# Wheelmod_rs485.net
KiCad netlist of a schematic drawn in EAGLE
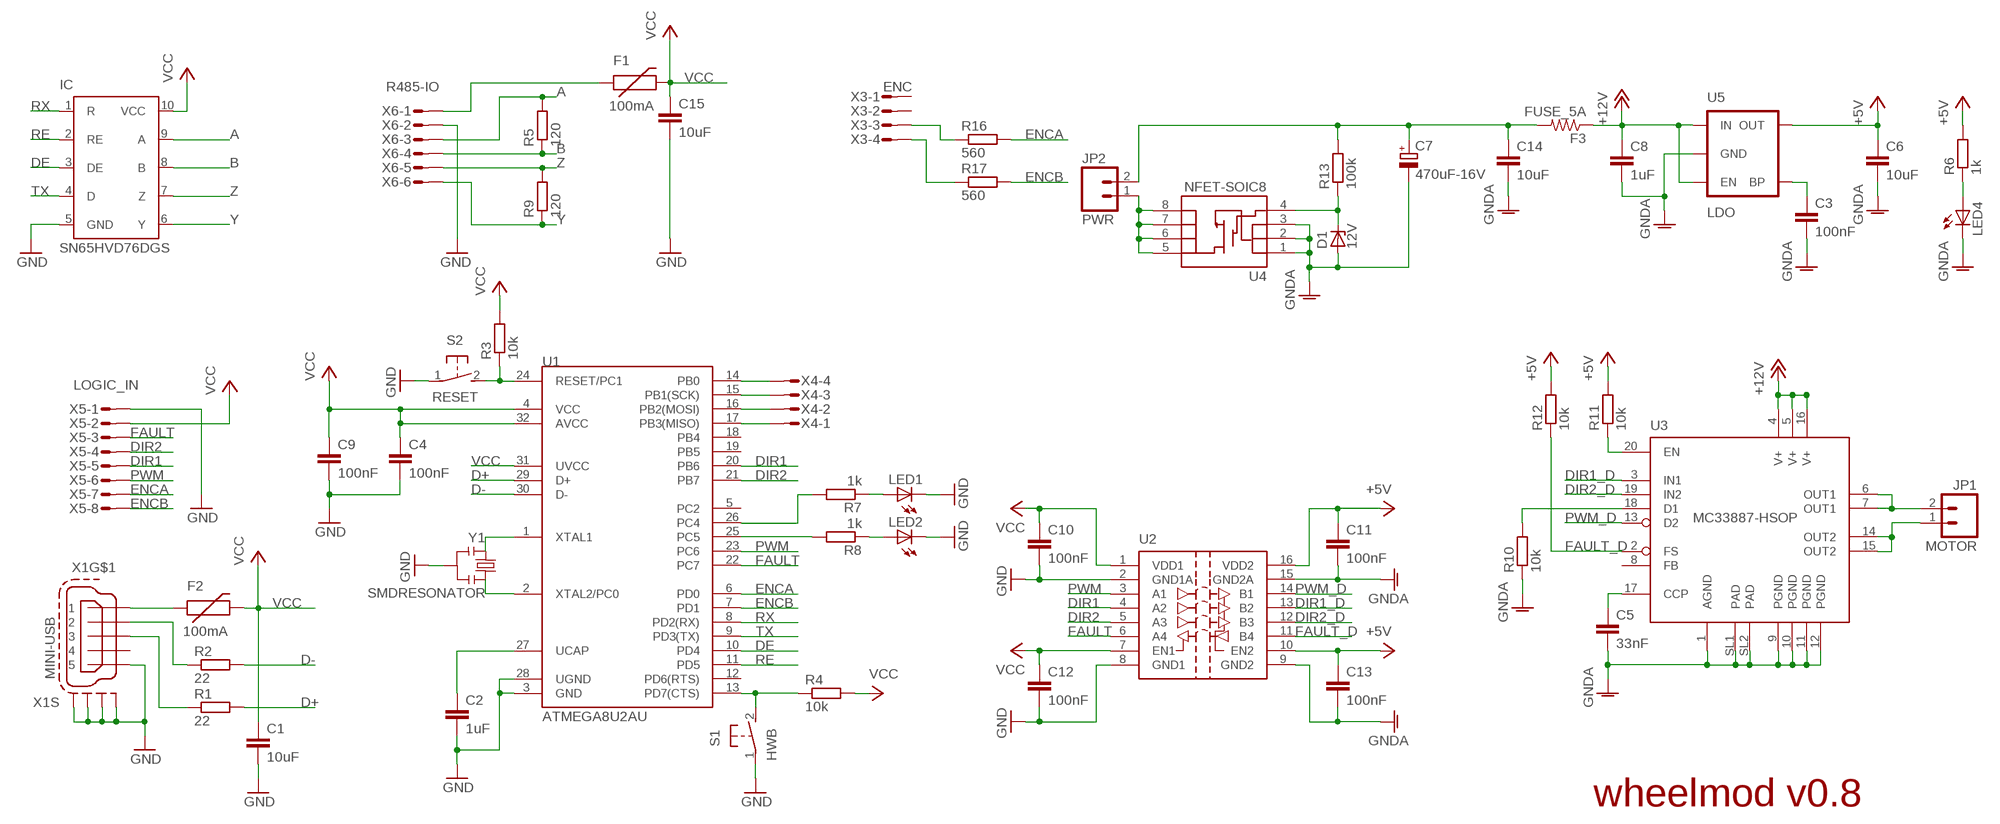
[diagram p0: schematic, sheet 1]

(export (version "E")
  (design (tool "Eeschema 10.0.6"))
  (components
    (comp (ref "C1")
      (value "10uF")
      (footprint "eagle-import:C1206K")
      (libsource (lib "eagle-import") (part "C-EUC1206K"))
    )
    (comp (ref "C2")
      (value "1uF")
      (footprint "eagle-import:C0603K")
      (libsource (lib "eagle-import") (part "C-EUC0603K"))
    )
    (comp (ref "C3")
      (value "100nF")
      (footprint "eagle-import:C0603K")
      (libsource (lib "eagle-import") (part "C-EUC0603K"))
    )
    (comp (ref "C4")
      (value "100nF")
      (footprint "eagle-import:C0603K")
      (libsource (lib "eagle-import") (part "C-EUC0603K"))
    )
    (comp (ref "C5")
      (value "33nF")
      (footprint "eagle-import:C0603K")
      (libsource (lib "eagle-import") (part "C-EUC0603K"))
    )
    (comp (ref "C6")
      (value "10uF")
      (footprint "eagle-import:C1206K")
      (libsource (lib "eagle-import") (part "C-EUC1206K"))
    )
    (comp (ref "C7")
      (value "470uF-16V")
      (footprint "eagle-import:E3,5-8")
      (libsource (lib "eagle-import") (part "CPOL-EUE3.5-8"))
    )
    (comp (ref "C8")
      (value "1uF")
      (footprint "eagle-import:C0603K")
      (libsource (lib "eagle-import") (part "C-EUC0603K"))
    )
    (comp (ref "C9")
      (value "100nF")
      (footprint "eagle-import:C0603K")
      (libsource (lib "eagle-import") (part "C-EUC0603K"))
    )
    (comp (ref "C10")
      (value "100nF")
      (footprint "eagle-import:C0603K")
      (libsource (lib "eagle-import") (part "C-EUC0603K"))
    )
    (comp (ref "C11")
      (value "100nF")
      (footprint "eagle-import:C0603K")
      (libsource (lib "eagle-import") (part "C-EUC0603K"))
    )
    (comp (ref "C12")
      (value "100nF")
      (footprint "eagle-import:C0603K")
      (libsource (lib "eagle-import") (part "C-EUC0603K"))
    )
    (comp (ref "C13")
      (value "100nF")
      (footprint "eagle-import:C0603K")
      (libsource (lib "eagle-import") (part "C-EUC0603K"))
    )
    (comp (ref "C14")
      (value "10uF")
      (footprint "eagle-import:C1206K")
      (libsource (lib "eagle-import") (part "C-EUC1206K"))
    )
    (comp (ref "C15")
      (value "10uF")
      (footprint "eagle-import:C1206K")
      (libsource (lib "eagle-import") (part "C-EUC1206K"))
    )
    (comp (ref "D1")
      (value "12V")
      (footprint "eagle-import:SOD123")
      (libsource (lib "eagle-import") (part "ZENER-DIODESOD123"))
    )
    (comp (ref "F1")
      (value "100mA")
      (footprint "eagle-import:PTC-1206")
      (libsource (lib "eagle-import") (part "PTCSMD"))
    )
    (comp (ref "F2")
      (value "100mA")
      (footprint "eagle-import:PTC-1206")
      (libsource (lib "eagle-import") (part "PTCSMD"))
    )
    (comp (ref "F3")
      (value "FUSE_5A")
      (footprint "eagle-import:R1206")
      (libsource (lib "eagle-import") (part "R-US_R1206"))
    )
    (comp (ref "JP1")
      (value "MOTOR")
      (footprint "eagle-import:SCREWTERMINAL-3.5MM-2")
      (libsource (lib "eagle-import") (part "M023.5MM"))
    )
    (comp (ref "JP2")
      (value "PWR")
      (footprint "eagle-import:SCREWTERMINAL-3.5MM-2")
      (libsource (lib "eagle-import") (part "M023.5MM"))
    )
    (comp (ref "LED1")
      (value "LEDCHIP-LED0603")
      (footprint "eagle-import:CHIP-LED0603")
      (libsource (lib "eagle-import") (part "LEDCHIP-LED0603"))
    )
    (comp (ref "LED2")
      (value "LEDCHIP-LED0603")
      (footprint "eagle-import:CHIP-LED0603")
      (libsource (lib "eagle-import") (part "LEDCHIP-LED0603"))
    )
    (comp (ref "LED4")
      (value "LEDCHIP-LED0603")
      (footprint "eagle-import:CHIP-LED0603")
      (libsource (lib "eagle-import") (part "LEDCHIP-LED0603"))
    )
    (comp (ref "R1")
      (value "22")
      (footprint "eagle-import:R0603")
      (libsource (lib "eagle-import") (part "R-EU_R0603"))
    )
    (comp (ref "R2")
      (value "22")
      (footprint "eagle-import:R0603")
      (libsource (lib "eagle-import") (part "R-EU_R0603"))
    )
    (comp (ref "R3")
      (value "10k")
      (footprint "eagle-import:R0603")
      (libsource (lib "eagle-import") (part "R-EU_R0603"))
    )
    (comp (ref "R4")
      (value "10k")
      (footprint "eagle-import:R0603")
      (libsource (lib "eagle-import") (part "R-EU_R0603"))
    )
    (comp (ref "R5")
      (value "120")
      (footprint "eagle-import:R0603")
      (libsource (lib "eagle-import") (part "R-EU_R0603"))
    )
    (comp (ref "R6")
      (value "1k")
      (footprint "eagle-import:R0603")
      (libsource (lib "eagle-import") (part "R-EU_R0603"))
    )
    (comp (ref "R7")
      (value "1k")
      (footprint "eagle-import:R0603")
      (libsource (lib "eagle-import") (part "R-EU_R0603"))
    )
    (comp (ref "R8")
      (value "1k")
      (footprint "eagle-import:R0603")
      (libsource (lib "eagle-import") (part "R-EU_R0603"))
    )
    (comp (ref "R9")
      (value "120")
      (footprint "eagle-import:R0603")
      (libsource (lib "eagle-import") (part "R-EU_R0603"))
    )
    (comp (ref "R10")
      (value "10k")
      (footprint "eagle-import:R0603")
      (libsource (lib "eagle-import") (part "R-EU_R0603"))
    )
    (comp (ref "R11")
      (value "10k")
      (footprint "eagle-import:R0603")
      (libsource (lib "eagle-import") (part "R-EU_R0603"))
    )
    (comp (ref "R12")
      (value "10k")
      (footprint "eagle-import:R0603")
      (libsource (lib "eagle-import") (part "R-EU_R0603"))
    )
    (comp (ref "R13")
      (value "100k")
      (footprint "eagle-import:R0603")
      (libsource (lib "eagle-import") (part "R-EU_R0603"))
    )
    (comp (ref "R16")
      (value "560")
      (footprint "eagle-import:R0603")
      (libsource (lib "eagle-import") (part "R-EU_R0603"))
    )
    (comp (ref "R17")
      (value "560")
      (footprint "eagle-import:R0603")
      (libsource (lib "eagle-import") (part "R-EU_R0603"))
    )
    (comp (ref "S1")
      (value "HWB")
      (footprint "eagle-import:ADTSM3")
      (libsource (lib "eagle-import") (part "ADTSM3"))
    )
    (comp (ref "S2")
      (value "RESET")
      (footprint "eagle-import:ADTSM3")
      (libsource (lib "eagle-import") (part "ADTSM3"))
    )
    (comp (ref "U$1")
      (value "SN65HVF76DGS")
      (footprint "eagle-import:MSOP10")
      (libsource (lib "eagle-import") (part "SN65HVF76DGS"))
    )
    (comp (ref "U1")
      (value "ATMEGA8U2AU")
      (footprint "eagle-import:TQFP32-08")
      (libsource (lib "eagle-import") (part "ATMEGA8U2AU"))
    )
    (comp (ref "U2")
      (value "SI8441IS1")
      (footprint "eagle-import:SO16")
      (libsource (lib "eagle-import") (part "SI8441IS1"))
    )
    (comp (ref "U3")
      (value "MC33887-HSOP")
      (footprint "eagle-import:HSOP")
      (libsource (lib "eagle-import") (part "MC33887-HSOP"))
    )
    (comp (ref "U4")
      (value "NFET-SOIC8")
      (footprint "eagle-import:SO08")
      (libsource (lib "eagle-import") (part "MOSFET-NCHANNEL-SOIC8"))
    )
    (comp (ref "U5")
      (value "LDO")
      (footprint "eagle-import:SOT23-5")
      (libsource (lib "eagle-import") (part "V_REG_LDOSMD"))
    )
    (comp (ref "X1")
      (value "MINI-USB")
      (footprint "eagle-import:32005-301")
      (libsource (lib "eagle-import") (part "MINI-USB-SCHIELD-32005-301"))
    )
    (comp (ref "X3")
      (value "ENC")
      (footprint "eagle-import:MICROMATCH-4")
      (fields (field (name "MPN") "7-215464-4"))
      (libsource (lib "eagle-import") (part "MICROMATCH-4"))
    )
    (comp (ref "X4")
      (value "MICROMATCH-4")
      (footprint "eagle-import:MICROMATCH-4")
      (fields (field (name "MPN") "7-215464-4"))
      (libsource (lib "eagle-import") (part "MICROMATCH-4"))
    )
    (comp (ref "X5")
      (value "LOGIC_IN")
      (footprint "eagle-import:MICROMATCH-8")
      (fields (field (name "MF") "FARNELL") (field (name "MPN") "7-215464-8"))
      (libsource (lib "eagle-import") (part "MICROMATCH-8"))
    )
    (comp (ref "X6")
      (value "R485-IO")
      (footprint "eagle-import:MICROMATCH-6")
      (fields (field (name "MPN") "7-215464-6"))
      (libsource (lib "eagle-import") (part "MICROMATCH-6"))
    )
    (comp (ref "Y1")
      (value "SMDRESONATOR")
      (footprint "eagle-import:PBRC-M")
      (libsource (lib "eagle-import") (part "SMDRESONATOR45X20"))
    )
  )
  (nets
    (net (code "1") (name "+5V") (class "Default")
      (node (ref "C11") (pin "1") (pinfunction "1_1") (pintype "passive"))
      (node (ref "C13") (pin "1") (pinfunction "1_1") (pintype "passive"))
      (node (ref "C6") (pin "1") (pinfunction "1_1") (pintype "passive"))
      (node (ref "R11") (pin "2") (pinfunction "2_2") (pintype "passive"))
      (node (ref "R12") (pin "2") (pinfunction "2_2") (pintype "passive"))
      (node (ref "R6") (pin "2") (pinfunction "2_2") (pintype "passive"))
      (node (ref "U2") (pin "10") (pinfunction "EN2_10") (pintype "input"))
      (node (ref "U2") (pin "16") (pinfunction "VDD2_16") (pintype "power_in"))
      (node (ref "U5") (pin "5") (pinfunction "OUT_5") (pintype "passive"))
    )
    (net (code "2") (name "+12V") (class "Default")
      (node (ref "C8") (pin "1") (pinfunction "1_1") (pintype "passive"))
      (node (ref "F3") (pin "1") (pinfunction "1_1") (pintype "passive"))
      (node (ref "U3") (pin "16") (pinfunction "V+_16") (pintype "power_in"))
      (node (ref "U3") (pin "4") (pinfunction "V+_4") (pintype "power_in"))
      (node (ref "U3") (pin "5") (pinfunction "V+_5") (pintype "power_in"))
      (node (ref "U5") (pin "1") (pinfunction "IN_1") (pintype "input"))
      (node (ref "U5") (pin "3") (pinfunction "EN_3") (pintype "input"))
    )
    (net (code "3") (name "/A") (class "Default")
      (node (ref "R5") (pin "2") (pinfunction "2_2") (pintype "passive"))
      (node (ref "U$1") (pin "9") (pinfunction "A_9") (pintype "input"))
      (node (ref "X6") (pin "3") (pinfunction "S_3") (pintype "passive"))
    )
    (net (code "4") (name "/B") (class "Default")
      (node (ref "R5") (pin "1") (pinfunction "1_1") (pintype "passive"))
      (node (ref "U$1") (pin "8") (pinfunction "B_8") (pintype "input"))
      (node (ref "X6") (pin "4") (pinfunction "S_4") (pintype "passive"))
    )
    (net (code "5") (name "/D+") (class "Default")
      (node (ref "R1") (pin "2") (pinfunction "2_2") (pintype "passive"))
      (node (ref "U1") (pin "29") (pinfunction "D+_29") (pintype "bidirectional"))
    )
    (net (code "6") (name "/D-") (class "Default")
      (node (ref "R2") (pin "2") (pinfunction "2_2") (pintype "passive"))
      (node (ref "U1") (pin "30") (pinfunction "D-_30") (pintype "bidirectional"))
    )
    (net (code "7") (name "/DE") (class "Default")
      (node (ref "U$1") (pin "3") (pinfunction "DE_3") (pintype "input"))
      (node (ref "U1") (pin "10") (pinfunction "PD4_10") (pintype "bidirectional"))
    )
    (net (code "8") (name "/DIR1") (class "Default")
      (node (ref "U1") (pin "20") (pinfunction "PB6_20") (pintype "bidirectional"))
      (node (ref "U2") (pin "4") (pinfunction "A2_4") (pintype "input"))
      (node (ref "X5") (pin "5") (pinfunction "S_5") (pintype "passive"))
    )
    (net (code "9") (name "/DIR1_D") (class "Default")
      (node (ref "U2") (pin "13") (pinfunction "B2_13") (pintype "output"))
      (node (ref "U3") (pin "3") (pinfunction "IN1_3") (pintype "input"))
    )
    (net (code "10") (name "/DIR2") (class "Default")
      (node (ref "U1") (pin "21") (pinfunction "PB7_21") (pintype "bidirectional"))
      (node (ref "U2") (pin "5") (pinfunction "A3_5") (pintype "input"))
      (node (ref "X5") (pin "4") (pinfunction "S_4") (pintype "passive"))
    )
    (net (code "11") (name "/DIR2_D") (class "Default")
      (node (ref "U2") (pin "12") (pinfunction "B3_12") (pintype "output"))
      (node (ref "U3") (pin "19") (pinfunction "IN2_19") (pintype "input"))
    )
    (net (code "12") (name "/ENCA") (class "Default")
      (node (ref "R16") (pin "2") (pinfunction "2_2") (pintype "passive"))
      (node (ref "U1") (pin "6") (pinfunction "PD0_6") (pintype "bidirectional"))
      (node (ref "X5") (pin "7") (pinfunction "S_7") (pintype "passive"))
    )
    (net (code "13") (name "/ENCB") (class "Default")
      (node (ref "R17") (pin "2") (pinfunction "2_2") (pintype "passive"))
      (node (ref "U1") (pin "7") (pinfunction "PD1_7") (pintype "bidirectional"))
      (node (ref "X5") (pin "8") (pinfunction "S_8") (pintype "passive"))
    )
    (net (code "14") (name "/FAULT") (class "Default")
      (node (ref "U1") (pin "22") (pinfunction "PC7_22") (pintype "bidirectional"))
      (node (ref "U2") (pin "6") (pinfunction "A4_6") (pintype "input"))
      (node (ref "X5") (pin "3") (pinfunction "S_3") (pintype "passive"))
    )
    (net (code "15") (name "/FAULT_D") (class "Default")
      (node (ref "R12") (pin "1") (pinfunction "1_1") (pintype "passive"))
      (node (ref "U2") (pin "11") (pinfunction "B4_11") (pintype "output"))
      (node (ref "U3") (pin "2") (pinfunction "FS_2") (pintype "open_collector"))
    )
    (net (code "16") (name "/PWM") (class "Default")
      (node (ref "U1") (pin "23") (pinfunction "PC6_23") (pintype "bidirectional"))
      (node (ref "U2") (pin "3") (pinfunction "A1_3") (pintype "input"))
      (node (ref "X5") (pin "6") (pinfunction "S_6") (pintype "passive"))
    )
    (net (code "17") (name "/PWM_D") (class "Default")
      (node (ref "U2") (pin "14") (pinfunction "B1_14") (pintype "output"))
      (node (ref "U3") (pin "13") (pinfunction "D2_13") (pintype "input"))
    )
    (net (code "18") (name "/RE") (class "Default")
      (node (ref "U$1") (pin "2") (pinfunction "RE_2") (pintype "input"))
      (node (ref "U1") (pin "11") (pinfunction "PD5_11") (pintype "bidirectional"))
    )
    (net (code "19") (name "/RX") (class "Default")
      (node (ref "U$1") (pin "1") (pinfunction "R_1") (pintype "output"))
      (node (ref "U1") (pin "8") (pinfunction "PD2(RX)_8") (pintype "bidirectional"))
    )
    (net (code "20") (name "/TX") (class "Default")
      (node (ref "U$1") (pin "4") (pinfunction "D_4") (pintype "input"))
      (node (ref "U1") (pin "9") (pinfunction "PD3(TX)_9") (pintype "bidirectional"))
    )
    (net (code "21") (name "/Y") (class "Default")
      (node (ref "R9") (pin "1") (pinfunction "1_1") (pintype "passive"))
      (node (ref "U$1") (pin "6") (pinfunction "Y_6") (pintype "output"))
      (node (ref "X6") (pin "6") (pinfunction "S_6") (pintype "passive"))
    )
    (net (code "22") (name "/Z") (class "Default")
      (node (ref "R9") (pin "2") (pinfunction "2_2") (pintype "passive"))
      (node (ref "U$1") (pin "7") (pinfunction "Z_7") (pintype "output"))
      (node (ref "X6") (pin "5") (pinfunction "S_5") (pintype "passive"))
    )
    (net (code "23") (name "GND") (class "Default")
      (node (ref "C1") (pin "2") (pinfunction "2_2") (pintype "passive"))
      (node (ref "C10") (pin "2") (pinfunction "2_2") (pintype "passive"))
      (node (ref "C12") (pin "2") (pinfunction "2_2") (pintype "passive"))
      (node (ref "C15") (pin "2") (pinfunction "2_2") (pintype "passive"))
      (node (ref "C2") (pin "2") (pinfunction "2_2") (pintype "passive"))
      (node (ref "C4") (pin "2") (pinfunction "2_2") (pintype "passive"))
      (node (ref "C9") (pin "2") (pinfunction "2_2") (pintype "passive"))
      (node (ref "LED1") (pin "C") (pinfunction "C_C") (pintype "passive"))
      (node (ref "LED2") (pin "C") (pinfunction "C_C") (pintype "passive"))
      (node (ref "S1") (pin "1") (pinfunction "1_1") (pintype "passive"))
      (node (ref "S2") (pin "1") (pinfunction "1_1") (pintype "passive"))
      (node (ref "U$1") (pin "5") (pinfunction "GND_5") (pintype "power_in"))
      (node (ref "U1") (pin "28") (pinfunction "UGND_28") (pintype "bidirectional"))
      (node (ref "U1") (pin "3") (pinfunction "GND_3") (pintype "bidirectional"))
      (node (ref "U2") (pin "2") (pinfunction "GND1A_2") (pintype "power_in"))
      (node (ref "U2") (pin "8") (pinfunction "GND1_8") (pintype "power_in"))
      (node (ref "X1") (pin "5") (pinfunction "5_5") (pintype "passive"))
      (node (ref "X1") (pin "M1") (pinfunction "S1_M1") (pintype "passive"))
      (node (ref "X1") (pin "M2") (pinfunction "S2_M2") (pintype "passive"))
      (node (ref "X1") (pin "M3") (pinfunction "S3_M3") (pintype "passive"))
      (node (ref "X1") (pin "M4") (pinfunction "S4_M4") (pintype "passive"))
      (node (ref "X5") (pin "1") (pinfunction "S_1") (pintype "passive"))
      (node (ref "X6") (pin "2") (pinfunction "S_2") (pintype "passive"))
      (node (ref "Y1") (pin "2") (pinfunction "P$2_2") (pintype "power_in"))
    )
    (net (code "24") (name "GNDA") (class "Default")
      (node (ref "C11") (pin "2") (pinfunction "2_2") (pintype "passive"))
      (node (ref "C13") (pin "2") (pinfunction "2_2") (pintype "passive"))
      (node (ref "C14") (pin "2") (pinfunction "2_2") (pintype "passive"))
      (node (ref "C3") (pin "2") (pinfunction "2_2") (pintype "passive"))
      (node (ref "C5") (pin "2") (pinfunction "2_2") (pintype "passive"))
      (node (ref "C6") (pin "2") (pinfunction "2_2") (pintype "passive"))
      (node (ref "C7") (pin "-") (pinfunction "-_-") (pintype "passive"))
      (node (ref "C8") (pin "2") (pinfunction "2_2") (pintype "passive"))
      (node (ref "D1") (pin "A") (pinfunction "A_A") (pintype "passive"))
      (node (ref "LED4") (pin "C") (pinfunction "C_C") (pintype "passive"))
      (node (ref "R10") (pin "1") (pinfunction "1_1") (pintype "passive"))
      (node (ref "U2") (pin "15") (pinfunction "GND2A_15") (pintype "power_in"))
      (node (ref "U2") (pin "9") (pinfunction "GND2_9") (pintype "power_in"))
      (node (ref "U3") (pin "1") (pinfunction "AGND_1") (pintype "power_in"))
      (node (ref "U3") (pin "10") (pinfunction "PGND_10") (pintype "power_in"))
      (node (ref "U3") (pin "11") (pinfunction "PGND_11") (pintype "power_in"))
      (node (ref "U3") (pin "12") (pinfunction "PGND_12") (pintype "power_in"))
      (node (ref "U3") (pin "9") (pinfunction "PGND_9") (pintype "power_in"))
      (node (ref "U3") (pin "SL1") (pinfunction "PAD_SL1") (pintype "passive"))
      (node (ref "U3") (pin "SL2") (pinfunction "PAD_SL2") (pintype "passive"))
      (node (ref "U4") (pin "1") (pinfunction "S_1") (pintype "bidirectional"))
      (node (ref "U4") (pin "2") (pinfunction "S_2") (pintype "bidirectional"))
      (node (ref "U4") (pin "3") (pinfunction "S_3") (pintype "bidirectional"))
      (node (ref "U5") (pin "2") (pinfunction "GND_2") (pintype "input"))
    )
    (net (code "25") (name "Net-(C14-Pad1)") (class "Default")
      (node (ref "C14") (pin "1") (pinfunction "1_1") (pintype "passive"))
      (node (ref "C7") (pin "+") (pinfunction "+_+") (pintype "passive"))
      (node (ref "F3") (pin "2") (pinfunction "2_2") (pintype "passive"))
      (node (ref "JP2") (pin "2") (pinfunction "2_2") (pintype "passive"))
      (node (ref "R13") (pin "2") (pinfunction "2_2") (pintype "passive"))
    )
    (net (code "26") (name "Net-(F2-Pad1)") (class "Default")
      (node (ref "F2") (pin "1") (pinfunction "1_1") (pintype "bidirectional"))
      (node (ref "X1") (pin "1") (pinfunction "1_1") (pintype "passive"))
    )
    (net (code "27") (name "Net-(JP1-Pad1)") (class "Default")
      (node (ref "JP1") (pin "1") (pinfunction "1_1") (pintype "passive"))
      (node (ref "U3") (pin "14") (pinfunction "OUT2_14") (pintype "bidirectional"))
      (node (ref "U3") (pin "15") (pinfunction "OUT2_15") (pintype "bidirectional"))
    )
    (net (code "28") (name "Net-(JP1-Pad2)") (class "Default")
      (node (ref "JP1") (pin "2") (pinfunction "2_2") (pintype "passive"))
      (node (ref "U3") (pin "6") (pinfunction "OUT1_6") (pintype "bidirectional"))
      (node (ref "U3") (pin "7") (pinfunction "OUT1_7") (pintype "bidirectional"))
    )
    (net (code "29") (name "Net-(JP2-Pad1)") (class "Default")
      (node (ref "JP2") (pin "1") (pinfunction "1_1") (pintype "passive"))
      (node (ref "U4") (pin "5") (pinfunction "D_5") (pintype "bidirectional"))
      (node (ref "U4") (pin "6") (pinfunction "D_6") (pintype "bidirectional"))
      (node (ref "U4") (pin "7") (pinfunction "D_7") (pintype "bidirectional"))
      (node (ref "U4") (pin "8") (pinfunction "D_8") (pintype "bidirectional"))
    )
    (net (code "30") (name "Net-(LED1-PadA)") (class "Default")
      (node (ref "LED1") (pin "A") (pinfunction "A_A") (pintype "passive"))
      (node (ref "R7") (pin "1") (pinfunction "1_1") (pintype "passive"))
    )
    (net (code "31") (name "Net-(LED2-PadA)") (class "Default")
      (node (ref "LED2") (pin "A") (pinfunction "A_A") (pintype "passive"))
      (node (ref "R8") (pin "1") (pinfunction "1_1") (pintype "passive"))
    )
    (net (code "32") (name "Net-(LED4-PadA)") (class "Default")
      (node (ref "LED4") (pin "A") (pinfunction "A_A") (pintype "passive"))
      (node (ref "R6") (pin "1") (pinfunction "1_1") (pintype "passive"))
    )
    (net (code "33") (name "Net-(R1-Pad1)") (class "Default")
      (node (ref "R1") (pin "1") (pinfunction "1_1") (pintype "passive"))
      (node (ref "X1") (pin "3") (pinfunction "3_3") (pintype "passive"))
    )
    (net (code "34") (name "Net-(R2-Pad1)") (class "Default")
      (node (ref "R2") (pin "1") (pinfunction "1_1") (pintype "passive"))
      (node (ref "X1") (pin "2") (pinfunction "2_2") (pintype "passive"))
    )
    (net (code "35") (name "Net-(U1-PB0)") (class "Default")
      (node (ref "U1") (pin "14") (pinfunction "PB0_14") (pintype "bidirectional"))
      (node (ref "X4") (pin "4") (pinfunction "S_4") (pintype "passive"))
    )
    (net (code "36") (name "Net-(U1-PB1(SCK))") (class "Default")
      (node (ref "U1") (pin "15") (pinfunction "PB1(SCK)_15") (pintype "bidirectional"))
      (node (ref "X4") (pin "3") (pinfunction "S_3") (pintype "passive"))
    )
    (net (code "37") (name "Net-(U1-PB2(MOSI))") (class "Default")
      (node (ref "U1") (pin "16") (pinfunction "PB2(MOSI)_16") (pintype "bidirectional"))
      (node (ref "X4") (pin "2") (pinfunction "S_2") (pintype "passive"))
    )
    (net (code "38") (name "Net-(U1-PB3(MISO))") (class "Default")
      (node (ref "U1") (pin "17") (pinfunction "PB3(MISO)_17") (pintype "bidirectional"))
      (node (ref "X4") (pin "1") (pinfunction "S_1") (pintype "passive"))
    )
    (net (code "39") (name "Net-(U1-PC4)") (class "Default")
      (node (ref "R7") (pin "2") (pinfunction "2_2") (pintype "passive"))
      (node (ref "U1") (pin "26") (pinfunction "PC4_26") (pintype "bidirectional"))
    )
    (net (code "40") (name "Net-(U1-PC5)") (class "Default")
      (node (ref "R8") (pin "2") (pinfunction "2_2") (pintype "passive"))
      (node (ref "U1") (pin "25") (pinfunction "PC5_25") (pintype "bidirectional"))
    )
    (net (code "41") (name "Net-(U1-PD7(CTS))") (class "Default")
      (node (ref "R4") (pin "1") (pinfunction "1_1") (pintype "passive"))
      (node (ref "S1") (pin "2") (pinfunction "2_2") (pintype "passive"))
      (node (ref "U1") (pin "13") (pinfunction "PD7(CTS)_13") (pintype "bidirectional"))
    )
    (net (code "42") (name "Net-(U1-RESET{slash}PC1)") (class "Default")
      (node (ref "R3") (pin "1") (pinfunction "1_1") (pintype "passive"))
      (node (ref "S2") (pin "2") (pinfunction "2_2") (pintype "passive"))
      (node (ref "U1") (pin "24") (pinfunction "RESET/PC1_24") (pintype "bidirectional"))
    )
    (net (code "43") (name "Net-(U1-UCAP)") (class "Default")
      (node (ref "C2") (pin "1") (pinfunction "1_1") (pintype "passive"))
      (node (ref "U1") (pin "27") (pinfunction "UCAP_27") (pintype "bidirectional"))
    )
    (net (code "44") (name "Net-(U1-XTAL1)") (class "Default")
      (node (ref "U1") (pin "1") (pinfunction "XTAL1_1") (pintype "bidirectional"))
      (node (ref "Y1") (pin "1") (pinfunction "P$1_1") (pintype "bidirectional"))
    )
    (net (code "45") (name "Net-(U1-XTAL2{slash}PC0)") (class "Default")
      (node (ref "U1") (pin "2") (pinfunction "XTAL2/PC0_2") (pintype "bidirectional"))
      (node (ref "Y1") (pin "3") (pinfunction "P$3_3") (pintype "bidirectional"))
    )
    (net (code "46") (name "Net-(U3-CCP)") (class "Default")
      (node (ref "C5") (pin "1") (pinfunction "1_1") (pintype "passive"))
      (node (ref "U3") (pin "17") (pinfunction "CCP_17") (pintype "passive"))
    )
    (net (code "47") (name "Net-(U3-D1)") (class "Default")
      (node (ref "R10") (pin "2") (pinfunction "2_2") (pintype "passive"))
      (node (ref "U3") (pin "18") (pinfunction "D1_18") (pintype "input"))
    )
    (net (code "48") (name "Net-(U3-EN)") (class "Default")
      (node (ref "R11") (pin "1") (pinfunction "1_1") (pintype "passive"))
      (node (ref "U3") (pin "20") (pinfunction "EN_20") (pintype "input"))
    )
    (net (code "49") (name "Net-(U4-G)") (class "Default")
      (node (ref "D1") (pin "C") (pinfunction "C_C") (pintype "passive"))
      (node (ref "R13") (pin "1") (pinfunction "1_1") (pintype "passive"))
      (node (ref "U4") (pin "4") (pinfunction "G_4") (pintype "bidirectional"))
    )
    (net (code "50") (name "Net-(U5-BP)") (class "Default")
      (node (ref "C3") (pin "1") (pinfunction "1_1") (pintype "passive"))
      (node (ref "U5") (pin "4") (pinfunction "BP_4") (pintype "input"))
    )
    (net (code "51") (name "Net-(X3C-S)") (class "Default")
      (node (ref "R16") (pin "1") (pinfunction "1_1") (pintype "passive"))
      (node (ref "X3") (pin "3") (pinfunction "S_3") (pintype "passive"))
    )
    (net (code "52") (name "Net-(X3D-S)") (class "Default")
      (node (ref "R17") (pin "1") (pinfunction "1_1") (pintype "passive"))
      (node (ref "X3") (pin "4") (pinfunction "S_4") (pintype "passive"))
    )
    (net (code "53") (name "Net-(X6A-S)") (class "Default")
      (node (ref "F1") (pin "1") (pinfunction "1_1") (pintype "bidirectional"))
      (node (ref "X6") (pin "1") (pinfunction "S_1") (pintype "passive"))
    )
    (net (code "54") (name "VCC") (class "Default")
      (node (ref "C1") (pin "1") (pinfunction "1_1") (pintype "passive"))
      (node (ref "C10") (pin "1") (pinfunction "1_1") (pintype "passive"))
      (node (ref "C12") (pin "1") (pinfunction "1_1") (pintype "passive"))
      (node (ref "C15") (pin "1") (pinfunction "1_1") (pintype "passive"))
      (node (ref "C4") (pin "1") (pinfunction "1_1") (pintype "passive"))
      (node (ref "C9") (pin "1") (pinfunction "1_1") (pintype "passive"))
      (node (ref "F1") (pin "2") (pinfunction "2_2") (pintype "bidirectional"))
      (node (ref "F2") (pin "2") (pinfunction "2_2") (pintype "bidirectional"))
      (node (ref "R3") (pin "2") (pinfunction "2_2") (pintype "passive"))
      (node (ref "R4") (pin "2") (pinfunction "2_2") (pintype "passive"))
      (node (ref "U$1") (pin "10") (pinfunction "VCC_10") (pintype "input"))
      (node (ref "U1") (pin "31") (pinfunction "UVCC_31") (pintype "bidirectional"))
      (node (ref "U1") (pin "32") (pinfunction "AVCC_32") (pintype "bidirectional"))
      (node (ref "U1") (pin "4") (pinfunction "VCC_4") (pintype "bidirectional"))
      (node (ref "U2") (pin "1") (pinfunction "VDD1_1") (pintype "power_in"))
      (node (ref "U2") (pin "7") (pinfunction "EN1_7") (pintype "input"))
      (node (ref "X5") (pin "2") (pinfunction "S_2") (pintype "passive"))
    )
    (net (code "55") (name "unconnected-(U1-PB4-Pad18)") (class "Default")
      (node (ref "U1") (pin "18") (pinfunction "PB4_18") (pintype "bidirectional"))
    )
    (net (code "56") (name "unconnected-(U1-PB5-Pad19)") (class "Default")
      (node (ref "U1") (pin "19") (pinfunction "PB5_19") (pintype "bidirectional"))
    )
    (net (code "57") (name "unconnected-(U1-PC2-Pad5)") (class "Default")
      (node (ref "U1") (pin "5") (pinfunction "PC2_5") (pintype "bidirectional"))
    )
    (net (code "58") (name "unconnected-(U1-PD6(RTS)-Pad12)") (class "Default")
      (node (ref "U1") (pin "12") (pinfunction "PD6(RTS)_12") (pintype "bidirectional"))
    )
    (net (code "59") (name "unconnected-(U3-FB-Pad8)") (class "Default")
      (node (ref "U3") (pin "8") (pinfunction "FB_8") (pintype "output"))
    )
    (net (code "60") (name "unconnected-(X1-Pad4)") (class "Default")
      (node (ref "X1") (pin "4") (pinfunction "4_4") (pintype "passive"))
    )
    (net (code "61") (name "unconnected-(X3A-S-Pad1)") (class "Default")
      (node (ref "X3") (pin "1") (pinfunction "S_1") (pintype "passive"))
    )
    (net (code "62") (name "unconnected-(X3B-S-Pad2)") (class "Default")
      (node (ref "X3") (pin "2") (pinfunction "S_2") (pintype "passive"))
    )
  )
)
